# relaisboard.net
KiCad netlist of a schematic drawn in EAGLE
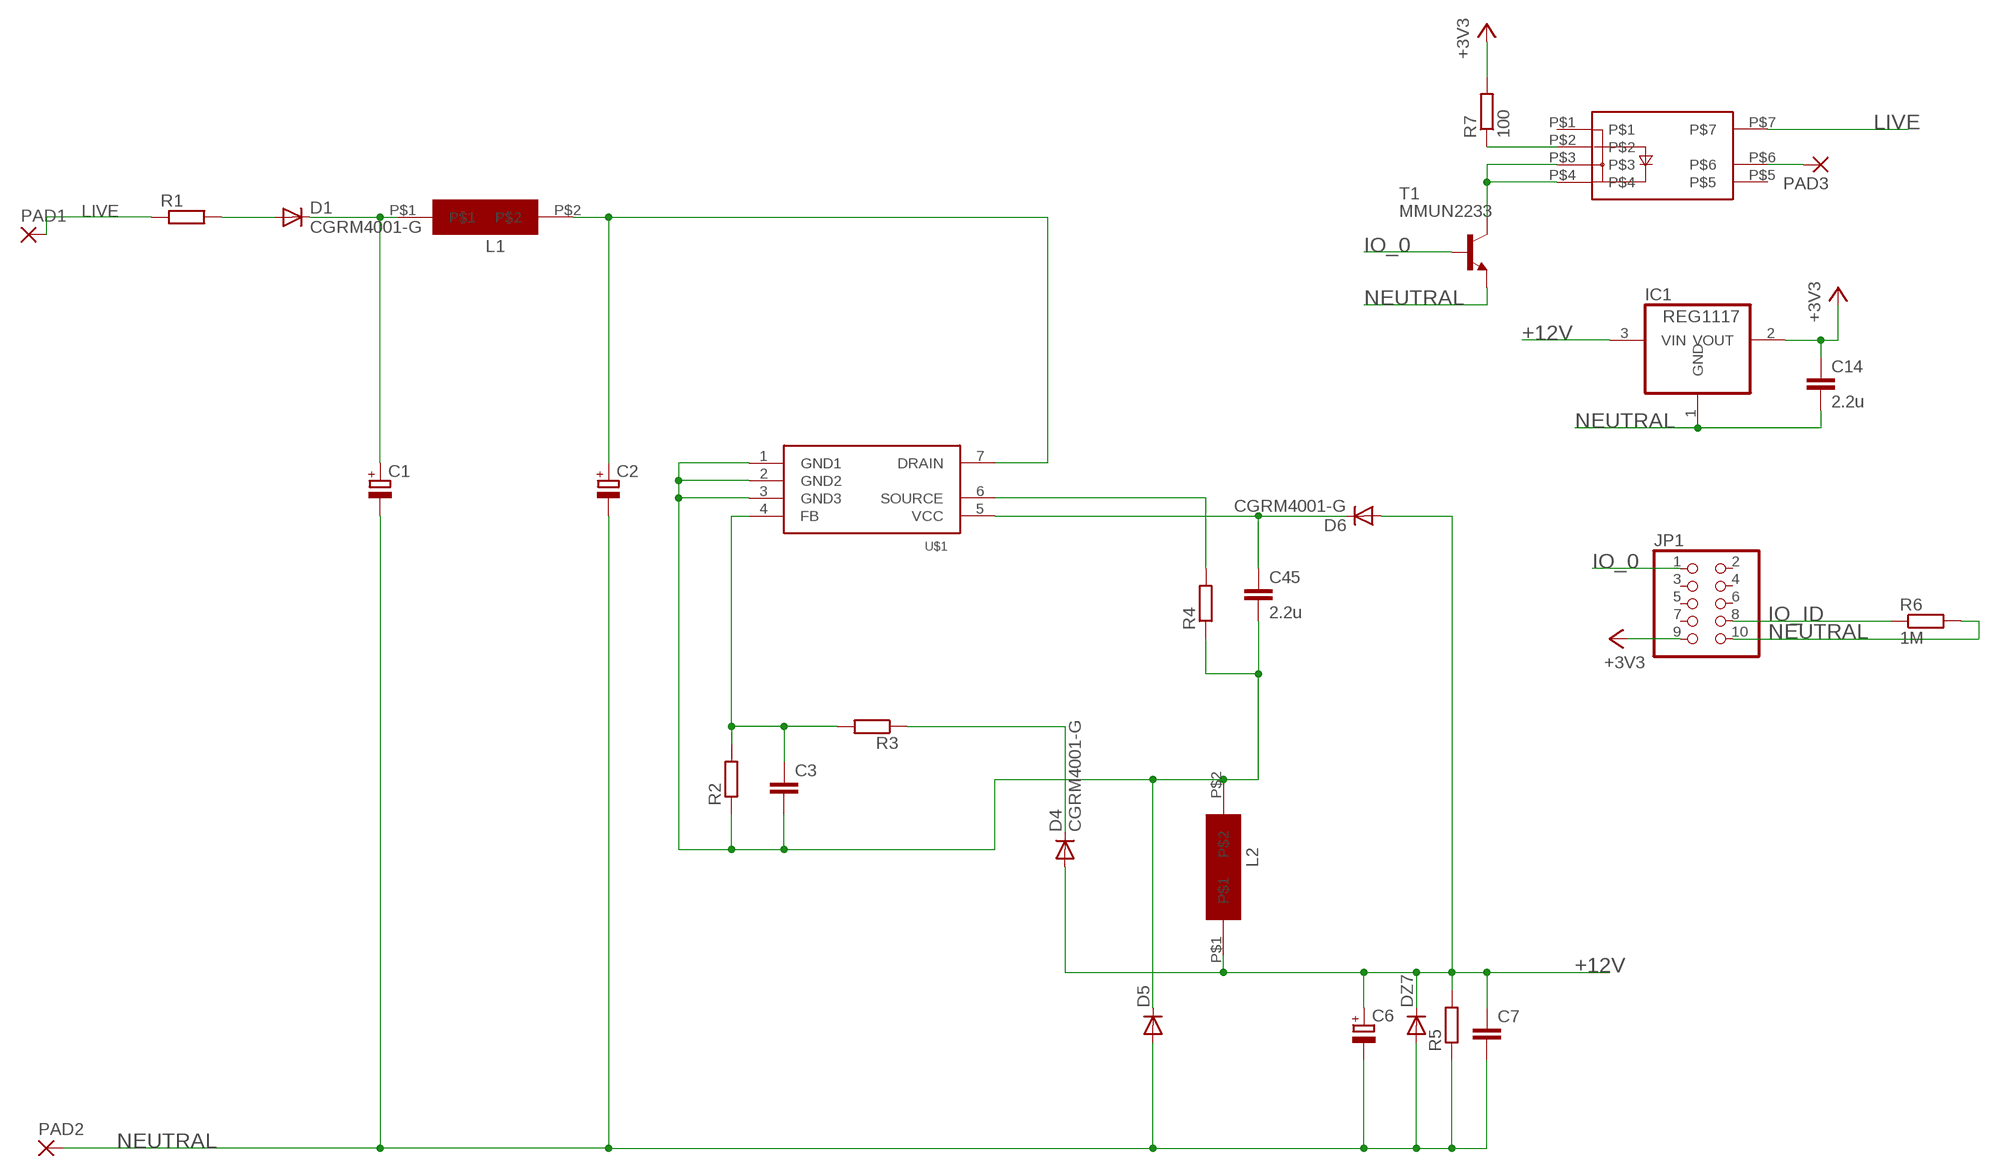
[diagram p0: schematic, sheet 1]

(export (version "E")
  (design (tool "Eeschema 10.0.6"))
  (components
    (comp (ref "C1")
      (value "CPOL-EUE5-8.5")
      (footprint "eagle-import:E5-8,5")
      (libsource (lib "eagle-import") (part "CPOL-EUE5-8.5"))
    )
    (comp (ref "C2")
      (value "CPOL-EUE5-8.5")
      (footprint "eagle-import:E5-8,5")
      (libsource (lib "eagle-import") (part "CPOL-EUE5-8.5"))
    )
    (comp (ref "C3")
      (value "C-EUC0603")
      (footprint "eagle-import:C0603")
      (libsource (lib "eagle-import") (part "C-EUC0603"))
    )
    (comp (ref "C6")
      (value "CPOL-EUE3.5-8")
      (footprint "eagle-import:E3,5-8")
      (libsource (lib "eagle-import") (part "CPOL-EUE3.5-8"))
    )
    (comp (ref "C7")
      (value "C-EUC0402")
      (footprint "eagle-import:C0402")
      (libsource (lib "eagle-import") (part "C-EUC0402"))
    )
    (comp (ref "C14")
      (value "2.2u")
      (footprint "eagle-import:C1206")
      (libsource (lib "eagle-import") (part "C-EUC1206"))
    )
    (comp (ref "C45")
      (value "2.2u")
      (footprint "eagle-import:C1206")
      (libsource (lib "eagle-import") (part "C-EUC1206"))
    )
    (comp (ref "D1")
      (value "CGRM4001-G")
      (footprint "eagle-import:SOD-123_MINI-SMA")
      (libsource (lib "eagle-import") (part "CGRM400-G1"))
    )
    (comp (ref "D4")
      (value "CGRM4001-G")
      (footprint "eagle-import:SOD-123_MINI-SMA")
      (libsource (lib "eagle-import") (part "CGRM400-G1"))
    )
    (comp (ref "D5")
      (value "DIODE-DO-214AC")
      (footprint "eagle-import:DO-214AC")
      (libsource (lib "eagle-import") (part "DIODE-DO-214AC"))
    )
    (comp (ref "D6")
      (value "CGRM4001-G")
      (footprint "eagle-import:SOD-123_MINI-SMA")
      (libsource (lib "eagle-import") (part "CGRM400-G1"))
    )
    (comp (ref "DZ7")
      (value "DIODE-SOD323-R")
      (footprint "eagle-import:SOD323-R")
      (libsource (lib "eagle-import") (part "DIODE-SOD323-R"))
    )
    (comp (ref "IC1")
      (value "REG1117")
      (footprint "eagle-import:SOT223")
      (libsource (lib "eagle-import") (part "REG1117"))
    )
    (comp (ref "JP1")
      (value "PINHD-2X5")
      (footprint "eagle-import:2X05")
      (libsource (lib "eagle-import") (part "PINHD-2X5"))
    )
    (comp (ref "L1")
      (value "INDUCTOR")
      (footprint "eagle-import:INDUCTOR")
      (libsource (lib "eagle-import") (part "INDUCTOR"))
    )
    (comp (ref "L2")
      (value "INDUCTOR")
      (footprint "eagle-import:INDUCTOR")
      (libsource (lib "eagle-import") (part "INDUCTOR"))
    )
    (comp (ref "PAD1")
      (value "2,15/1,0")
      (footprint "eagle-import:2,15_1,0")
      (libsource (lib "eagle-import") (part "2,15/1,0"))
    )
    (comp (ref "PAD2")
      (value "2,15/1,0")
      (footprint "eagle-import:2,15_1,0")
      (libsource (lib "eagle-import") (part "2,15/1,0"))
    )
    (comp (ref "PAD3")
      (value "2,15/1,0")
      (footprint "eagle-import:2,15_1,0")
      (libsource (lib "eagle-import") (part "2,15/1,0"))
    )
    (comp (ref "R1")
      (value "R-EU_0207/2V")
      (footprint "eagle-import:0207_2V")
      (libsource (lib "eagle-import") (part "R-EU_0207/2V"))
    )
    (comp (ref "R2")
      (value "R-EU_R0402")
      (footprint "eagle-import:R0402")
      (libsource (lib "eagle-import") (part "R-EU_R0402"))
    )
    (comp (ref "R3")
      (value "R-EU_R0402")
      (footprint "eagle-import:R0402")
      (libsource (lib "eagle-import") (part "R-EU_R0402"))
    )
    (comp (ref "R4")
      (value "R-EU_R1206")
      (footprint "eagle-import:R1206")
      (libsource (lib "eagle-import") (part "R-EU_R1206"))
    )
    (comp (ref "R5")
      (value "R-EU_R0603")
      (footprint "eagle-import:R0603")
      (libsource (lib "eagle-import") (part "R-EU_R0603"))
    )
    (comp (ref "R6")
      (value "1M")
      (footprint "eagle-import:R0402")
      (libsource (lib "eagle-import") (part "R-EU_R0402"))
    )
    (comp (ref "R7")
      (value "100")
      (footprint "eagle-import:R0402")
      (libsource (lib "eagle-import") (part "R-EU_R0402"))
    )
    (comp (ref "T1")
      (value "MMUN2233")
      (footprint "eagle-import:SOT23-BEC")
      (libsource (lib "eagle-import") (part "-NPN-SOT23-BECBC817-16"))
    )
    (comp (ref "U$1")
      (value "TEA1721")
      (footprint "eagle-import:SO7")
      (libsource (lib "eagle-import") (part "TEA1721"))
    )
    (comp (ref "U$2")
      (value "PR3BMF51")
      (footprint "eagle-import:DIP7")
      (libsource (lib "eagle-import") (part "PR3BMF51"))
    )
  )
  (nets
    (net (code "1") (name "+3V3") (class "Default")
      (node (ref "C14") (pin "1") (pinfunction "1_1") (pintype "passive"))
      (node (ref "IC1") (pin "2") (pinfunction "VOUT_2") (pintype "output"))
      (node (ref "JP1") (pin "9") (pinfunction "9_9") (pintype "passive"))
      (node (ref "R7") (pin "2") (pinfunction "2_2") (pintype "passive"))
    )
    (net (code "2") (name "/+12V") (class "Default")
      (node (ref "C6") (pin "+") (pinfunction "+_+") (pintype "passive"))
      (node (ref "C7") (pin "1") (pinfunction "1_1") (pintype "passive"))
      (node (ref "D4") (pin "A") (pinfunction "A_A") (pintype "passive"))
      (node (ref "D6") (pin "A") (pinfunction "A_A") (pintype "passive"))
      (node (ref "DZ7") (pin "C") (pinfunction "C_C") (pintype "passive"))
      (node (ref "IC1") (pin "3") (pinfunction "VIN_3") (pintype "input"))
      (node (ref "L2") (pin "P$1") (pinfunction "P$1_P$1") (pintype "bidirectional"))
      (node (ref "R5") (pin "2") (pinfunction "2_2") (pintype "passive"))
    )
    (net (code "3") (name "/IO_0") (class "Default")
      (node (ref "JP1") (pin "1") (pinfunction "1_1") (pintype "passive"))
      (node (ref "T1") (pin "B") (pinfunction "B_B") (pintype "passive"))
    )
    (net (code "4") (name "/IO_ID") (class "Default")
      (node (ref "JP1") (pin "8") (pinfunction "8_8") (pintype "passive"))
      (node (ref "R6") (pin "1") (pinfunction "1_1") (pintype "passive"))
    )
    (net (code "5") (name "/LIVE") (class "Default")
      (node (ref "PAD1") (pin "1") (pinfunction "P_1") (pintype "passive"))
      (node (ref "R1") (pin "1") (pinfunction "1_1") (pintype "passive"))
      (node (ref "U$2") (pin "P$7") (pinfunction "P$7_P$7") (pintype "bidirectional"))
    )
    (net (code "6") (name "/NEUTRAL") (class "Default")
      (node (ref "C1") (pin "-") (pinfunction "-_-") (pintype "passive"))
      (node (ref "C14") (pin "2") (pinfunction "2_2") (pintype "passive"))
      (node (ref "C2") (pin "-") (pinfunction "-_-") (pintype "passive"))
      (node (ref "C6") (pin "-") (pinfunction "-_-") (pintype "passive"))
      (node (ref "C7") (pin "2") (pinfunction "2_2") (pintype "passive"))
      (node (ref "D5") (pin "A") (pinfunction "A_A") (pintype "passive"))
      (node (ref "DZ7") (pin "A") (pinfunction "A_A") (pintype "passive"))
      (node (ref "IC1") (pin "1") (pinfunction "GND_1") (pintype "power_in"))
      (node (ref "JP1") (pin "10") (pinfunction "10_10") (pintype "passive"))
      (node (ref "PAD2") (pin "1") (pinfunction "P_1") (pintype "passive"))
      (node (ref "R5") (pin "1") (pinfunction "1_1") (pintype "passive"))
      (node (ref "R6") (pin "2") (pinfunction "2_2") (pintype "passive"))
      (node (ref "T1") (pin "E") (pinfunction "E_E") (pintype "passive"))
    )
    (net (code "7") (name "Net-(C1-Pad+)") (class "Default")
      (node (ref "C1") (pin "+") (pinfunction "+_+") (pintype "passive"))
      (node (ref "D1") (pin "C") (pinfunction "C_C") (pintype "passive"))
      (node (ref "L1") (pin "P$1") (pinfunction "P$1_P$1") (pintype "bidirectional"))
    )
    (net (code "8") (name "Net-(D1-PadA)") (class "Default")
      (node (ref "D1") (pin "A") (pinfunction "A_A") (pintype "passive"))
      (node (ref "R1") (pin "2") (pinfunction "2_2") (pintype "passive"))
    )
    (net (code "9") (name "Net-(D4-PadC)") (class "Default")
      (node (ref "D4") (pin "C") (pinfunction "C_C") (pintype "passive"))
      (node (ref "R3") (pin "1") (pinfunction "1_1") (pintype "passive"))
    )
    (net (code "10") (name "Net-(PAD3-P)") (class "Default")
      (node (ref "PAD3") (pin "1") (pinfunction "P_1") (pintype "passive"))
      (node (ref "U$2") (pin "P$6") (pinfunction "P$6_P$6") (pintype "bidirectional"))
    )
    (net (code "11") (name "Net-(R7-Pad1)") (class "Default")
      (node (ref "R7") (pin "1") (pinfunction "1_1") (pintype "passive"))
      (node (ref "U$2") (pin "P$2") (pinfunction "P$2_P$2") (pintype "bidirectional"))
    )
    (net (code "12") (name "Net-(T1-PadC)") (class "Default")
      (node (ref "T1") (pin "C") (pinfunction "C_C") (pintype "passive"))
      (node (ref "U$2") (pin "P$3") (pinfunction "P$3_P$3") (pintype "bidirectional"))
      (node (ref "U$2") (pin "P$4") (pinfunction "P$4_P$4") (pintype "bidirectional"))
    )
    (net (code "13") (name "Net-(U$1-DRAIN)") (class "Default")
      (node (ref "C2") (pin "+") (pinfunction "+_+") (pintype "passive"))
      (node (ref "L1") (pin "P$2") (pinfunction "P$2_P$2") (pintype "bidirectional"))
      (node (ref "U$1") (pin "7") (pinfunction "DRAIN_7") (pintype "bidirectional"))
    )
    (net (code "14") (name "Net-(U$1-FB)") (class "Default")
      (node (ref "C3") (pin "1") (pinfunction "1_1") (pintype "passive"))
      (node (ref "R2") (pin "2") (pinfunction "2_2") (pintype "passive"))
      (node (ref "R3") (pin "2") (pinfunction "2_2") (pintype "passive"))
      (node (ref "U$1") (pin "4") (pinfunction "FB_4") (pintype "bidirectional"))
    )
    (net (code "15") (name "Net-(U$1-GND1)") (class "Default")
      (node (ref "C3") (pin "2") (pinfunction "2_2") (pintype "passive"))
      (node (ref "C45") (pin "2") (pinfunction "2_2") (pintype "passive"))
      (node (ref "D5") (pin "C") (pinfunction "C_C") (pintype "passive"))
      (node (ref "L2") (pin "P$2") (pinfunction "P$2_P$2") (pintype "bidirectional"))
      (node (ref "R2") (pin "1") (pinfunction "1_1") (pintype "passive"))
      (node (ref "R4") (pin "1") (pinfunction "1_1") (pintype "passive"))
      (node (ref "U$1") (pin "1") (pinfunction "GND1_1") (pintype "bidirectional"))
      (node (ref "U$1") (pin "2") (pinfunction "GND2_2") (pintype "bidirectional"))
      (node (ref "U$1") (pin "3") (pinfunction "GND3_3") (pintype "bidirectional"))
    )
    (net (code "16") (name "Net-(U$1-SOURCE)") (class "Default")
      (node (ref "R4") (pin "2") (pinfunction "2_2") (pintype "passive"))
      (node (ref "U$1") (pin "6") (pinfunction "SOURCE_6") (pintype "bidirectional"))
    )
    (net (code "17") (name "Net-(U$1-VCC)") (class "Default")
      (node (ref "C45") (pin "1") (pinfunction "1_1") (pintype "passive"))
      (node (ref "D6") (pin "C") (pinfunction "C_C") (pintype "passive"))
      (node (ref "U$1") (pin "5") (pinfunction "VCC_5") (pintype "bidirectional"))
    )
    (net (code "18") (name "unconnected-(JP1-Pad2)") (class "Default")
      (node (ref "JP1") (pin "2") (pinfunction "2_2") (pintype "passive"))
    )
    (net (code "19") (name "unconnected-(JP1-Pad3)") (class "Default")
      (node (ref "JP1") (pin "3") (pinfunction "3_3") (pintype "passive"))
    )
    (net (code "20") (name "unconnected-(JP1-Pad4)") (class "Default")
      (node (ref "JP1") (pin "4") (pinfunction "4_4") (pintype "passive"))
    )
    (net (code "21") (name "unconnected-(JP1-Pad5)") (class "Default")
      (node (ref "JP1") (pin "5") (pinfunction "5_5") (pintype "passive"))
    )
    (net (code "22") (name "unconnected-(JP1-Pad6)") (class "Default")
      (node (ref "JP1") (pin "6") (pinfunction "6_6") (pintype "passive"))
    )
    (net (code "23") (name "unconnected-(JP1-Pad7)") (class "Default")
      (node (ref "JP1") (pin "7") (pinfunction "7_7") (pintype "passive"))
    )
    (net (code "24") (name "unconnected-(U$2-PadP$1)") (class "Default")
      (node (ref "U$2") (pin "P$1") (pinfunction "P$1_P$1") (pintype "bidirectional"))
    )
    (net (code "25") (name "unconnected-(U$2-PadP$5)") (class "Default")
      (node (ref "U$2") (pin "P$5") (pinfunction "P$5_P$5") (pintype "bidirectional"))
    )
  )
)
